# main_schematic.net
KiCad netlist of a schematic drawn in Altium Designer
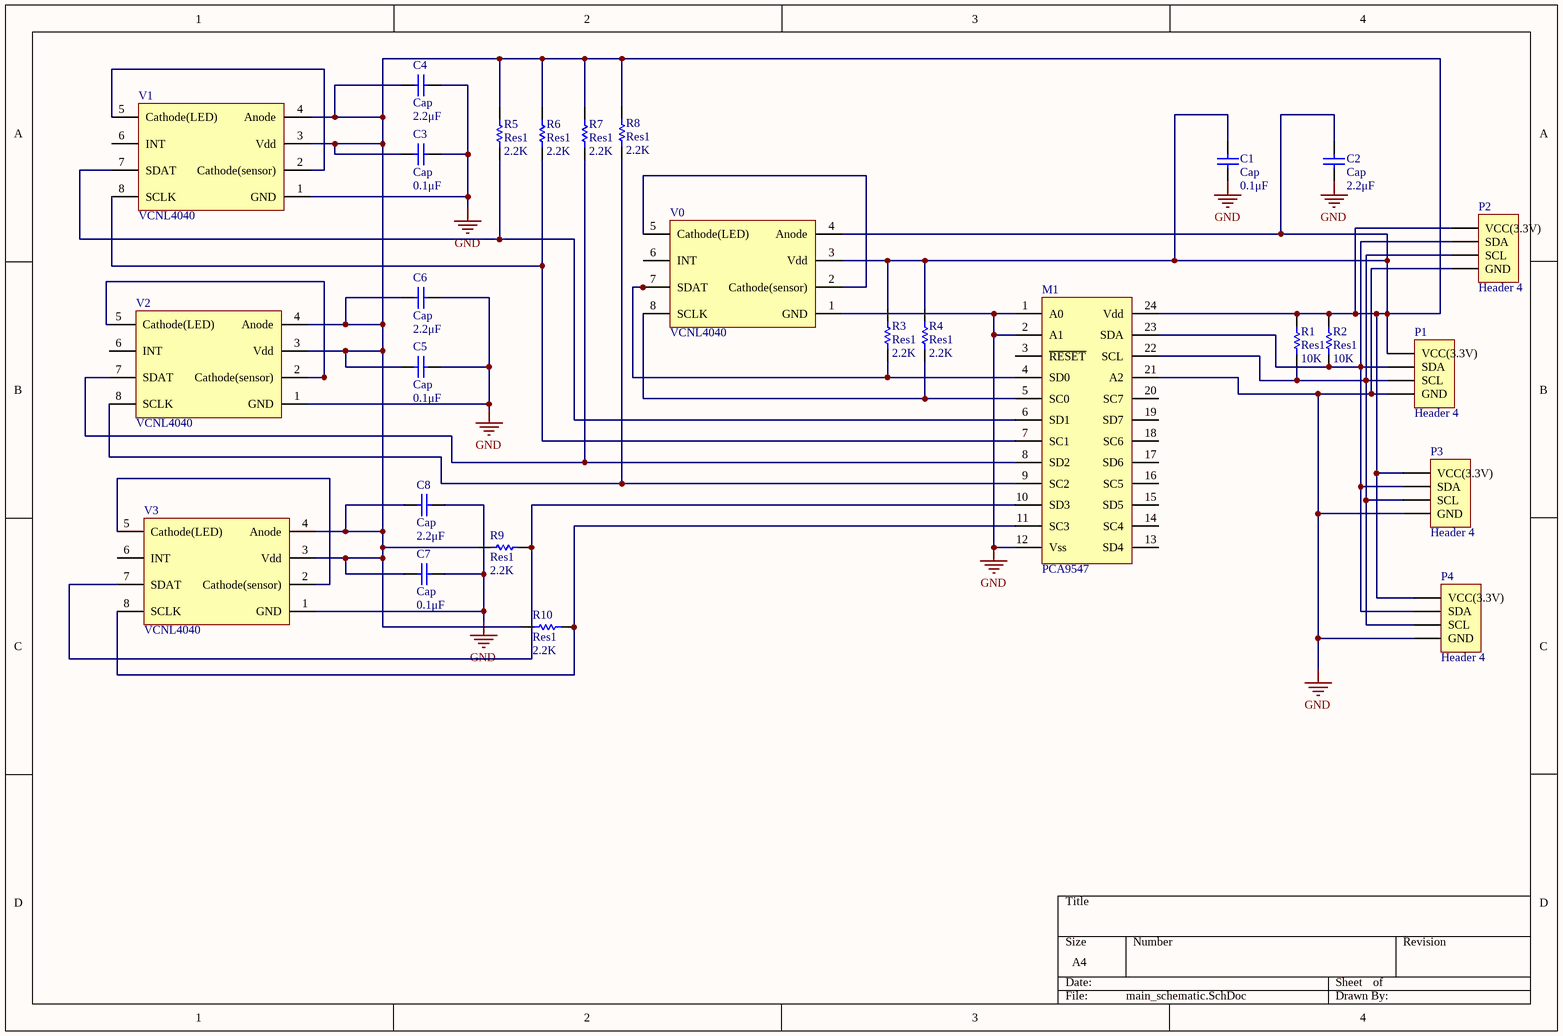
[diagram p0: main_schematic.SchDoc]

(export (version "E")
  (design (tool "Eeschema 10.0.6"))
  (components
    (comp (ref "C1")
      (value "Cap")
      (footprint "1608[0603]")
      (description "Capacitor")
      (fields (field (name "ALTIUM_VALUE") "0.1μF") (field (name "PUBLISHER") "Altium Limited"))
      (libsource (lib "Miscellaneous Devices") (part "Cap"))
    )
    (comp (ref "C2")
      (value "Cap")
      (footprint "1608[0603]")
      (description "Capacitor")
      (fields (field (name "ALTIUM_VALUE") "2.2μF") (field (name "PUBLISHER") "Altium Limited"))
      (libsource (lib "Miscellaneous Devices") (part "Cap"))
    )
    (comp (ref "C3")
      (value "Cap")
      (footprint "1608[0603]")
      (description "Capacitor")
      (fields (field (name "ALTIUM_VALUE") "0.1μF") (field (name "PUBLISHER") "Altium Limited"))
      (libsource (lib "Miscellaneous Devices") (part "Cap"))
    )
    (comp (ref "C4")
      (value "Cap")
      (footprint "1608[0603]")
      (description "Capacitor")
      (fields (field (name "ALTIUM_VALUE") "2.2μF") (field (name "PUBLISHER") "Altium Limited"))
      (libsource (lib "Miscellaneous Devices") (part "Cap"))
    )
    (comp (ref "C5")
      (value "Cap")
      (footprint "1608[0603]")
      (description "Capacitor")
      (fields (field (name "ALTIUM_VALUE") "0.1μF") (field (name "PUBLISHER") "Altium Limited"))
      (libsource (lib "Miscellaneous Devices") (part "Cap"))
    )
    (comp (ref "C6")
      (value "Cap")
      (footprint "1608[0603]")
      (description "Capacitor")
      (fields (field (name "ALTIUM_VALUE") "2.2μF") (field (name "PUBLISHER") "Altium Limited"))
      (libsource (lib "Miscellaneous Devices") (part "Cap"))
    )
    (comp (ref "C7")
      (value "Cap")
      (footprint "1608[0603]")
      (description "Capacitor")
      (fields (field (name "ALTIUM_VALUE") "0.1μF") (field (name "PUBLISHER") "Altium Limited"))
      (libsource (lib "Miscellaneous Devices") (part "Cap"))
    )
    (comp (ref "C8")
      (value "Cap")
      (footprint "1608[0603]")
      (description "Capacitor")
      (fields (field (name "ALTIUM_VALUE") "2.2μF") (field (name "PUBLISHER") "Altium Limited"))
      (libsource (lib "Miscellaneous Devices") (part "Cap"))
    )
    (comp (ref "M1") (value "PCA9547") (footprint "TSSOP24") (libsource (lib "PCA9547") (part "PCA9547")))
    (comp (ref "P1")
      (value "Header 4")
      (footprint "HDR1X4")
      (description "Header, 4-Pin")
      (fields (field (name "PUBLISHER") "Altium Limited"))
      (libsource (lib "Miscellaneous Connectors") (part "Header 4"))
    )
    (comp (ref "P2")
      (value "Header 4")
      (footprint "HDR1X4")
      (description "Header, 4-Pin")
      (fields (field (name "PUBLISHER") "Altium Limited"))
      (libsource (lib "Miscellaneous Connectors") (part "Header 4"))
    )
    (comp (ref "P3")
      (value "Header 4")
      (footprint "HDR1X4")
      (description "Header, 4-Pin")
      (fields (field (name "PUBLISHER") "Altium Limited"))
      (libsource (lib "Miscellaneous Connectors") (part "Header 4"))
    )
    (comp (ref "P4")
      (value "Header 4")
      (footprint "HDR1X4")
      (description "Header, 4-Pin")
      (fields (field (name "PUBLISHER") "Altium Limited"))
      (libsource (lib "Miscellaneous Connectors") (part "Header 4"))
    )
    (comp (ref "R1")
      (value "Res1")
      (footprint "1608[0603]")
      (description "Resistor")
      (fields (field (name "ALTIUM_VALUE") "10K") (field (name "PUBLISHER") "Altium Limited"))
      (libsource (lib "Miscellaneous Devices") (part "Res1"))
    )
    (comp (ref "R2")
      (value "Res1")
      (footprint "1608[0603]")
      (description "Resistor")
      (fields (field (name "ALTIUM_VALUE") "10K") (field (name "PUBLISHER") "Altium Limited"))
      (libsource (lib "Miscellaneous Devices") (part "Res1"))
    )
    (comp (ref "R3")
      (value "Res1")
      (footprint "1608[0603]")
      (description "Resistor")
      (fields (field (name "ALTIUM_VALUE") "2.2K") (field (name "PUBLISHER") "Altium Limited"))
      (libsource (lib "Miscellaneous Devices") (part "Res1"))
    )
    (comp (ref "R4")
      (value "Res1")
      (footprint "1608[0603]")
      (description "Resistor")
      (fields (field (name "ALTIUM_VALUE") "2.2K") (field (name "PUBLISHER") "Altium Limited"))
      (libsource (lib "Miscellaneous Devices") (part "Res1"))
    )
    (comp (ref "R5")
      (value "Res1")
      (footprint "1608[0603]")
      (description "Resistor")
      (fields (field (name "ALTIUM_VALUE") "2.2K") (field (name "PUBLISHER") "Altium Limited"))
      (libsource (lib "Miscellaneous Devices") (part "Res1"))
    )
    (comp (ref "R6")
      (value "Res1")
      (footprint "1608[0603]")
      (description "Resistor")
      (fields (field (name "ALTIUM_VALUE") "2.2K") (field (name "PUBLISHER") "Altium Limited"))
      (libsource (lib "Miscellaneous Devices") (part "Res1"))
    )
    (comp (ref "R7")
      (value "Res1")
      (footprint "1608[0603]")
      (description "Resistor")
      (fields (field (name "ALTIUM_VALUE") "2.2K") (field (name "PUBLISHER") "Altium Limited"))
      (libsource (lib "Miscellaneous Devices") (part "Res1"))
    )
    (comp (ref "R8")
      (value "Res1")
      (footprint "1608[0603]")
      (description "Resistor")
      (fields (field (name "ALTIUM_VALUE") "2.2K") (field (name "PUBLISHER") "Altium Limited"))
      (libsource (lib "Miscellaneous Devices") (part "Res1"))
    )
    (comp (ref "R9")
      (value "Res1")
      (footprint "1608[0603]")
      (description "Resistor")
      (fields (field (name "ALTIUM_VALUE") "2.2K") (field (name "PUBLISHER") "Altium Limited"))
      (libsource (lib "Miscellaneous Devices") (part "Res1"))
    )
    (comp (ref "R10")
      (value "Res1")
      (footprint "1608[0603]")
      (description "Resistor")
      (fields (field (name "ALTIUM_VALUE") "2.2K") (field (name "PUBLISHER") "Altium Limited"))
      (libsource (lib "Miscellaneous Devices") (part "Res1"))
    )
    (comp (ref "V0") (value "VCNL4040") (footprint "SOP8") (libsource (lib "VCNL4040") (part "Component_1")))
    (comp (ref "V1") (value "VCNL4040") (footprint "SOP8") (libsource (lib "VCNL4040") (part "Component_1")))
    (comp (ref "V2") (value "VCNL4040") (footprint "SOP8") (libsource (lib "VCNL4040") (part "Component_1")))
    (comp (ref "V3") (value "VCNL4040") (footprint "SOP8") (libsource (lib "VCNL4040") (part "Component_1")))
  )
  (nets
    (net (code "1") (name "GND") (class "Default")
      (node (ref "C1") (pin "1") (pinfunction "1_1") (pintype "passive"))
      (node (ref "C2") (pin "1") (pinfunction "1_1") (pintype "passive"))
      (node (ref "C3") (pin "1") (pinfunction "1_1") (pintype "passive"))
      (node (ref "C4") (pin "1") (pinfunction "1_1") (pintype "passive"))
      (node (ref "C5") (pin "1") (pinfunction "1_1") (pintype "passive"))
      (node (ref "C6") (pin "1") (pinfunction "1_1") (pintype "passive"))
      (node (ref "C7") (pin "1") (pinfunction "1_1") (pintype "passive"))
      (node (ref "C8") (pin "1") (pinfunction "1_1") (pintype "passive"))
      (node (ref "M1") (pin "1") (pinfunction "A0_1") (pintype "passive"))
      (node (ref "M1") (pin "12") (pinfunction "Vss_12") (pintype "passive"))
      (node (ref "M1") (pin "2") (pinfunction "A1_2") (pintype "passive"))
      (node (ref "M1") (pin "21") (pinfunction "A2_21") (pintype "passive"))
      (node (ref "P1") (pin "4") (pinfunction "GND_4") (pintype "passive"))
      (node (ref "P2") (pin "4") (pinfunction "GND_4") (pintype "passive"))
      (node (ref "P3") (pin "4") (pinfunction "GND_4") (pintype "passive"))
      (node (ref "P4") (pin "4") (pinfunction "GND_4") (pintype "passive"))
      (node (ref "V0") (pin "1") (pinfunction "GND_1") (pintype "passive"))
      (node (ref "V1") (pin "1") (pinfunction "GND_1") (pintype "passive"))
      (node (ref "V2") (pin "1") (pinfunction "GND_1") (pintype "passive"))
      (node (ref "V3") (pin "1") (pinfunction "GND_1") (pintype "passive"))
    )
    (net (code "2") (name "Net-(M1-SC0)") (class "Default")
      (node (ref "M1") (pin "5") (pinfunction "SC0_5") (pintype "passive"))
      (node (ref "R4") (pin "1") (pinfunction "1_1") (pintype "passive"))
      (node (ref "V0") (pin "8") (pinfunction "SCLK_8") (pintype "passive"))
    )
    (net (code "3") (name "Net-(M1-SC1)") (class "Default")
      (node (ref "M1") (pin "7") (pinfunction "SC1_7") (pintype "passive"))
      (node (ref "R6") (pin "1") (pinfunction "1_1") (pintype "passive"))
      (node (ref "V1") (pin "8") (pinfunction "SCLK_8") (pintype "passive"))
    )
    (net (code "4") (name "Net-(M1-SC2)") (class "Default")
      (node (ref "M1") (pin "9") (pinfunction "SC2_9") (pintype "passive"))
      (node (ref "R8") (pin "1") (pinfunction "1_1") (pintype "passive"))
      (node (ref "V2") (pin "8") (pinfunction "SCLK_8") (pintype "passive"))
    )
    (net (code "5") (name "Net-(M1-SC3)") (class "Default")
      (node (ref "M1") (pin "11") (pinfunction "SC3_11") (pintype "passive"))
      (node (ref "R10") (pin "1") (pinfunction "1_1") (pintype "passive"))
      (node (ref "V3") (pin "8") (pinfunction "SCLK_8") (pintype "passive"))
    )
    (net (code "6") (name "Net-(M1-SCL)") (class "Default")
      (node (ref "M1") (pin "22") (pinfunction "SCL_22") (pintype "passive"))
      (node (ref "P1") (pin "3") (pinfunction "SCL_3") (pintype "passive"))
      (node (ref "P2") (pin "3") (pinfunction "SCL_3") (pintype "passive"))
      (node (ref "P3") (pin "3") (pinfunction "SCL_3") (pintype "passive"))
      (node (ref "P4") (pin "3") (pinfunction "SCL_3") (pintype "passive"))
      (node (ref "R1") (pin "1") (pinfunction "1_1") (pintype "passive"))
    )
    (net (code "7") (name "Net-(M1-SD0)") (class "Default")
      (node (ref "M1") (pin "4") (pinfunction "SD0_4") (pintype "passive"))
      (node (ref "R3") (pin "1") (pinfunction "1_1") (pintype "passive"))
      (node (ref "V0") (pin "7") (pinfunction "SDAT_7") (pintype "passive"))
    )
    (net (code "8") (name "Net-(M1-SD1)") (class "Default")
      (node (ref "M1") (pin "6") (pinfunction "SD1_6") (pintype "passive"))
      (node (ref "R5") (pin "1") (pinfunction "1_1") (pintype "passive"))
      (node (ref "V1") (pin "7") (pinfunction "SDAT_7") (pintype "passive"))
    )
    (net (code "9") (name "Net-(M1-SD2)") (class "Default")
      (node (ref "M1") (pin "8") (pinfunction "SD2_8") (pintype "passive"))
      (node (ref "R7") (pin "1") (pinfunction "1_1") (pintype "passive"))
      (node (ref "V2") (pin "7") (pinfunction "SDAT_7") (pintype "passive"))
    )
    (net (code "10") (name "Net-(M1-SD3)") (class "Default")
      (node (ref "M1") (pin "10") (pinfunction "SD3_10") (pintype "passive"))
      (node (ref "R9") (pin "1") (pinfunction "1_1") (pintype "passive"))
      (node (ref "V3") (pin "7") (pinfunction "SDAT_7") (pintype "passive"))
    )
    (net (code "11") (name "Net-(M1-SDA)") (class "Default")
      (node (ref "M1") (pin "23") (pinfunction "SDA_23") (pintype "passive"))
      (node (ref "P1") (pin "2") (pinfunction "SDA_2") (pintype "passive"))
      (node (ref "P2") (pin "2") (pinfunction "SDA_2") (pintype "passive"))
      (node (ref "P3") (pin "2") (pinfunction "SDA_2") (pintype "passive"))
      (node (ref "P4") (pin "2") (pinfunction "SDA_2") (pintype "passive"))
      (node (ref "R2") (pin "1") (pinfunction "1_1") (pintype "passive"))
    )
    (net (code "12") (name "Net-(M1-Vdd)") (class "Default")
      (node (ref "C1") (pin "2") (pinfunction "2_2") (pintype "passive"))
      (node (ref "C2") (pin "2") (pinfunction "2_2") (pintype "passive"))
      (node (ref "C3") (pin "2") (pinfunction "2_2") (pintype "passive"))
      (node (ref "C4") (pin "2") (pinfunction "2_2") (pintype "passive"))
      (node (ref "C5") (pin "2") (pinfunction "2_2") (pintype "passive"))
      (node (ref "C6") (pin "2") (pinfunction "2_2") (pintype "passive"))
      (node (ref "C7") (pin "2") (pinfunction "2_2") (pintype "passive"))
      (node (ref "C8") (pin "2") (pinfunction "2_2") (pintype "passive"))
      (node (ref "M1") (pin "24") (pinfunction "Vdd_24") (pintype "passive"))
      (node (ref "P1") (pin "1") (pinfunction "VCC(3.3V)_1") (pintype "passive"))
      (node (ref "P2") (pin "1") (pinfunction "VCC(3.3V)_1") (pintype "passive"))
      (node (ref "P3") (pin "1") (pinfunction "VCC(3.3V)_1") (pintype "passive"))
      (node (ref "P4") (pin "1") (pinfunction "VCC(3.3V)_1") (pintype "passive"))
      (node (ref "R1") (pin "2") (pinfunction "2_2") (pintype "passive"))
      (node (ref "R10") (pin "2") (pinfunction "2_2") (pintype "passive"))
      (node (ref "R2") (pin "2") (pinfunction "2_2") (pintype "passive"))
      (node (ref "R3") (pin "2") (pinfunction "2_2") (pintype "passive"))
      (node (ref "R4") (pin "2") (pinfunction "2_2") (pintype "passive"))
      (node (ref "R5") (pin "2") (pinfunction "2_2") (pintype "passive"))
      (node (ref "R6") (pin "2") (pinfunction "2_2") (pintype "passive"))
      (node (ref "R7") (pin "2") (pinfunction "2_2") (pintype "passive"))
      (node (ref "R8") (pin "2") (pinfunction "2_2") (pintype "passive"))
      (node (ref "R9") (pin "2") (pinfunction "2_2") (pintype "passive"))
      (node (ref "V0") (pin "3") (pinfunction "Vdd_3") (pintype "passive"))
      (node (ref "V0") (pin "4") (pinfunction "Anode_4") (pintype "passive"))
      (node (ref "V1") (pin "3") (pinfunction "Vdd_3") (pintype "passive"))
      (node (ref "V1") (pin "4") (pinfunction "Anode_4") (pintype "passive"))
      (node (ref "V2") (pin "3") (pinfunction "Vdd_3") (pintype "passive"))
      (node (ref "V2") (pin "4") (pinfunction "Anode_4") (pintype "passive"))
      (node (ref "V3") (pin "3") (pinfunction "Vdd_3") (pintype "passive"))
      (node (ref "V3") (pin "4") (pinfunction "Anode_4") (pintype "passive"))
    )
    (net (code "13") (name "Net-(V0-Cathode(LED))") (class "Default")
      (node (ref "V0") (pin "2") (pinfunction "Cathode(sensor)_2") (pintype "passive"))
      (node (ref "V0") (pin "5") (pinfunction "Cathode(LED)_5") (pintype "passive"))
    )
    (net (code "14") (name "Net-(V1-Cathode(LED))") (class "Default")
      (node (ref "V1") (pin "2") (pinfunction "Cathode(sensor)_2") (pintype "passive"))
      (node (ref "V1") (pin "5") (pinfunction "Cathode(LED)_5") (pintype "passive"))
    )
    (net (code "15") (name "Net-(V2-Cathode(LED))") (class "Default")
      (node (ref "V2") (pin "2") (pinfunction "Cathode(sensor)_2") (pintype "passive"))
      (node (ref "V2") (pin "5") (pinfunction "Cathode(LED)_5") (pintype "passive"))
    )
    (net (code "16") (name "Net-(V3-Cathode(LED))") (class "Default")
      (node (ref "V3") (pin "2") (pinfunction "Cathode(sensor)_2") (pintype "passive"))
      (node (ref "V3") (pin "5") (pinfunction "Cathode(LED)_5") (pintype "passive"))
    )
    (net (code "17") (name "unconnected-(M1-SC4-Pad14)") (class "Default")
      (node (ref "M1") (pin "14") (pinfunction "SC4_14") (pintype "passive"))
    )
    (net (code "18") (name "unconnected-(M1-SC5-Pad16)") (class "Default")
      (node (ref "M1") (pin "16") (pinfunction "SC5_16") (pintype "passive"))
    )
    (net (code "19") (name "unconnected-(M1-SC6-Pad18)") (class "Default")
      (node (ref "M1") (pin "18") (pinfunction "SC6_18") (pintype "passive"))
    )
    (net (code "20") (name "unconnected-(M1-SC7-Pad20)") (class "Default")
      (node (ref "M1") (pin "20") (pinfunction "SC7_20") (pintype "passive"))
    )
    (net (code "21") (name "unconnected-(M1-SD4-Pad13)") (class "Default")
      (node (ref "M1") (pin "13") (pinfunction "SD4_13") (pintype "passive"))
    )
    (net (code "22") (name "unconnected-(M1-SD5-Pad15)") (class "Default")
      (node (ref "M1") (pin "15") (pinfunction "SD5_15") (pintype "passive"))
    )
    (net (code "23") (name "unconnected-(M1-SD6-Pad17)") (class "Default")
      (node (ref "M1") (pin "17") (pinfunction "SD6_17") (pintype "passive"))
    )
    (net (code "24") (name "unconnected-(M1-SD7-Pad19)") (class "Default")
      (node (ref "M1") (pin "19") (pinfunction "SD7_19") (pintype "passive"))
    )
    (net (code "25") (name "unconnected-(M1-~{RESET}-Pad3)") (class "Default")
      (node (ref "M1") (pin "3") (pinfunction "~{RESET}_3") (pintype "passive"))
    )
    (net (code "26") (name "unconnected-(V0-INT-Pad6)") (class "Default")
      (node (ref "V0") (pin "6") (pinfunction "INT_6") (pintype "passive"))
    )
    (net (code "27") (name "unconnected-(V1-INT-Pad6)") (class "Default")
      (node (ref "V1") (pin "6") (pinfunction "INT_6") (pintype "passive"))
    )
    (net (code "28") (name "unconnected-(V2-INT-Pad6)") (class "Default")
      (node (ref "V2") (pin "6") (pinfunction "INT_6") (pintype "passive"))
    )
    (net (code "29") (name "unconnected-(V3-INT-Pad6)") (class "Default")
      (node (ref "V3") (pin "6") (pinfunction "INT_6") (pintype "passive"))
    )
  )
)
